# STM32Fx.net
KiCad netlist of a schematic drawn in Altium Designer
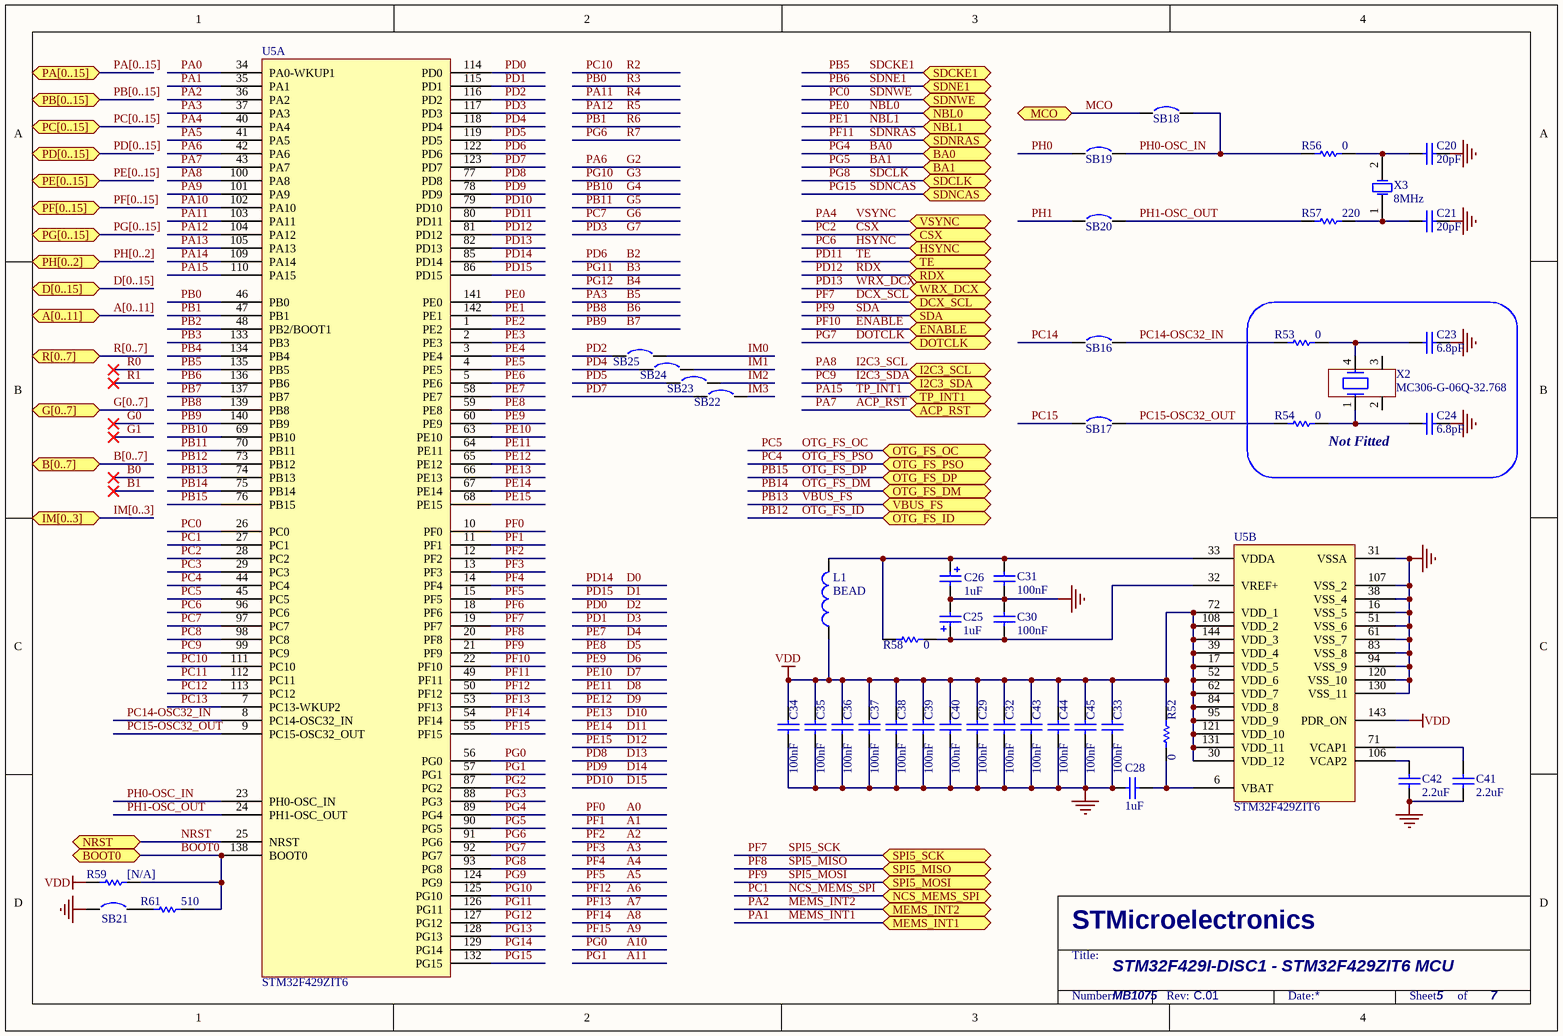
[diagram p0: STM32Fx.SchDoc]

(export (version "E")
  (design (tool "Eeschema 10.0.6"))
  (components
    (comp (ref "C20")
      (value "20pF")
      (footprint "0402C")
      (description "Capacitor 0402 / 0603 / 0805")
      (libsource (lib "MCD_TOOLS") (part "Capacitor_ST"))
    )
    (comp (ref "C21")
      (value "20pF")
      (footprint "0402C")
      (description "Capacitor 0402 / 0603 / 0805")
      (libsource (lib "MCD_TOOLS") (part "Capacitor_ST"))
    )
    (comp (ref "C23")
      (value "6.8pF")
      (footprint "0402C")
      (description "Capacitor 0402 / 0603 / 0805")
      (libsource (lib "MCD_TOOLS") (part "Capacitor_ST"))
    )
    (comp (ref "C24")
      (value "6.8pF")
      (footprint "0402C")
      (description "Capacitor 0402 / 0603 / 0805")
      (libsource (lib "MCD_TOOLS") (part "Capacitor_ST"))
    )
    (comp (ref "C25")
      (value "1uF")
      (footprint "TAN-A")
      (description "Polarized Capacitor (Radial)")
      (fields (field (name "PUBLISHER") "Altium Limited"))
      (libsource (lib "Miscellaneous Devices") (part "Cap Pol1"))
    )
    (comp (ref "C26")
      (value "1uF")
      (footprint "TAN-A")
      (description "Polarized Capacitor (Radial)")
      (fields (field (name "PUBLISHER") "Altium Limited"))
      (libsource (lib "Miscellaneous Devices") (part "Cap Pol1"))
    )
    (comp (ref "C28")
      (value "1uF")
      (footprint "0603C")
      (description "Capacitor 0402 / 0603 / 0805")
      (libsource (lib "MCD_TOOLS") (part "Capacitor_ST"))
    )
    (comp (ref "C29")
      (value "100nF")
      (footprint "0402C")
      (description "Capacitor 0402 / 0603 / 0805")
      (libsource (lib "MCD_TOOLS") (part "Capacitor_ST"))
    )
    (comp (ref "C30")
      (value "100nF")
      (footprint "0402C")
      (description "Capacitor 0402 / 0603 / 0805")
      (libsource (lib "MCD_TOOLS") (part "Capacitor_ST"))
    )
    (comp (ref "C31")
      (value "100nF")
      (footprint "0402C")
      (description "Capacitor 0402 / 0603 / 0805")
      (libsource (lib "MCD_TOOLS") (part "Capacitor_ST"))
    )
    (comp (ref "C32")
      (value "100nF")
      (footprint "0402C")
      (description "Capacitor 0402 / 0603 / 0805")
      (libsource (lib "MCD_TOOLS") (part "Capacitor_ST"))
    )
    (comp (ref "C33")
      (value "100nF")
      (footprint "0402C")
      (description "Capacitor 0402 / 0603 / 0805")
      (libsource (lib "MCD_TOOLS") (part "Capacitor_ST"))
    )
    (comp (ref "C34")
      (value "100nF")
      (footprint "0402C")
      (description "Capacitor 0402 / 0603 / 0805")
      (libsource (lib "MCD_TOOLS") (part "Capacitor_ST"))
    )
    (comp (ref "C35")
      (value "100nF")
      (footprint "0402C")
      (description "Capacitor 0402 / 0603 / 0805")
      (libsource (lib "MCD_TOOLS") (part "Capacitor_ST"))
    )
    (comp (ref "C36")
      (value "100nF")
      (footprint "0402C")
      (description "Capacitor 0402 / 0603 / 0805")
      (libsource (lib "MCD_TOOLS") (part "Capacitor_ST"))
    )
    (comp (ref "C37")
      (value "100nF")
      (footprint "0402C")
      (description "Capacitor 0402 / 0603 / 0805")
      (libsource (lib "MCD_TOOLS") (part "Capacitor_ST"))
    )
    (comp (ref "C38")
      (value "100nF")
      (footprint "0402C")
      (description "Capacitor 0402 / 0603 / 0805")
      (libsource (lib "MCD_TOOLS") (part "Capacitor_ST"))
    )
    (comp (ref "C39")
      (value "100nF")
      (footprint "0402C")
      (description "Capacitor 0402 / 0603 / 0805")
      (libsource (lib "MCD_TOOLS") (part "Capacitor_ST"))
    )
    (comp (ref "C40")
      (value "100nF")
      (footprint "0402C")
      (description "Capacitor 0402 / 0603 / 0805")
      (libsource (lib "MCD_TOOLS") (part "Capacitor_ST"))
    )
    (comp (ref "C41")
      (value "2.2uF")
      (footprint "TAN-A")
      (description "Low ESR Ceramic Capacitor (X7R)")
      (libsource (lib "MCD_TOOLS") (part "Cap Low ESR"))
    )
    (comp (ref "C42")
      (value "2.2uF")
      (footprint "TAN-A")
      (description "Low ESR Ceramic Capacitor (X7R)")
      (libsource (lib "MCD_TOOLS") (part "Cap Low ESR"))
    )
    (comp (ref "C43")
      (value "100nF")
      (footprint "0402C")
      (description "Capacitor 0402 / 0603 / 0805")
      (libsource (lib "MCD_TOOLS") (part "Capacitor_ST"))
    )
    (comp (ref "C44")
      (value "100nF")
      (footprint "0402C")
      (description "Capacitor 0402 / 0603 / 0805")
      (libsource (lib "MCD_TOOLS") (part "Capacitor_ST"))
    )
    (comp (ref "C45")
      (value "100nF")
      (footprint "0402C")
      (description "Capacitor 0402 / 0603 / 0805")
      (libsource (lib "MCD_TOOLS") (part "Capacitor_ST"))
    )
    (comp (ref "L1")
      (value "BEAD")
      (footprint "0603L")
      (description "Inductor")
      (fields (field (name "PUBLISHER") "Altium Limited"))
      (libsource (lib "MCD_TOOLS") (part "Inductor"))
    )
    (comp (ref "R52")
      (value "0")
      (footprint "0402R")
      (description "Resistor 0402 or 0603 or 0805")
      (libsource (lib "MCD_TOOLS") (part "Resistor_ST"))
    )
    (comp (ref "R53")
      (value "0")
      (footprint "0402R")
      (description "Resistor 0402 or 0603 or 0805")
      (libsource (lib "MCD_TOOLS") (part "Resistor_ST"))
    )
    (comp (ref "R54")
      (value "0")
      (footprint "0402R")
      (description "Resistor 0402 or 0603 or 0805")
      (libsource (lib "MCD_TOOLS") (part "Resistor_ST"))
    )
    (comp (ref "R56")
      (value "0")
      (footprint "0402R")
      (description "Resistor 0402 or 0603 or 0805")
      (libsource (lib "MCD_TOOLS") (part "Resistor_ST"))
    )
    (comp (ref "R57")
      (value "220")
      (footprint "0402R")
      (description "Resistor 0402 or 0603 or 0805")
      (libsource (lib "MCD_TOOLS") (part "Resistor_ST"))
    )
    (comp (ref "R58")
      (value "0")
      (footprint "0402R")
      (description "Resistor 0402 or 0603 or 0805")
      (libsource (lib "MCD_TOOLS") (part "Resistor_ST"))
    )
    (comp (ref "R59")
      (value "[N/A]")
      (footprint "0402R")
      (description "Resistor 0402 or 0603 or 0805")
      (libsource (lib "MCD_TOOLS") (part "Resistor_ST"))
    )
    (comp (ref "R61")
      (value "510")
      (footprint "0402R")
      (description "Resistor 0402 or 0603 or 0805")
      (libsource (lib "MCD_TOOLS") (part "Resistor_ST"))
    )
    (comp (ref "SB16")
      (value "Circuit Breaker")
      (footprint "JP2_SMD")
      (fields (field (name "PUBLISHER") "Altium Limited"))
      (libsource (lib "MB915") (part "Circuit Breaker"))
    )
    (comp (ref "SB17")
      (value "Circuit Breaker")
      (footprint "JP2_SMD")
      (fields (field (name "PUBLISHER") "Altium Limited"))
      (libsource (lib "MB915") (part "Circuit Breaker"))
    )
    (comp (ref "SB18")
      (value "Circuit Breaker")
      (footprint "JP2_SMD")
      (fields (field (name "PUBLISHER") "Altium Limited"))
      (libsource (lib "MB915") (part "Circuit Breaker"))
    )
    (comp (ref "SB19")
      (value "Circuit Breaker")
      (footprint "JP2_SMD")
      (fields (field (name "PUBLISHER") "Altium Limited"))
      (libsource (lib "MB915") (part "Circuit Breaker"))
    )
    (comp (ref "SB20")
      (value "Circuit Breaker")
      (footprint "JP2_SMD")
      (fields (field (name "PUBLISHER") "Altium Limited"))
      (libsource (lib "MB915") (part "Circuit Breaker"))
    )
    (comp (ref "SB21")
      (value "Circuit Breaker")
      (footprint "JP2_SMD")
      (fields (field (name "PUBLISHER") "Altium Limited"))
      (libsource (lib "MB915") (part "Circuit Breaker"))
    )
    (comp (ref "SB22")
      (value "Circuit Breaker")
      (footprint "JP2_SMD")
      (fields (field (name "PUBLISHER") "Altium Limited"))
      (libsource (lib "MB915") (part "Circuit Breaker"))
    )
    (comp (ref "SB23")
      (value "Circuit Breaker")
      (footprint "JP2_SMD")
      (fields (field (name "PUBLISHER") "Altium Limited"))
      (libsource (lib "MB915") (part "Circuit Breaker"))
    )
    (comp (ref "SB24")
      (value "Circuit Breaker")
      (footprint "JP2_SMD")
      (fields (field (name "PUBLISHER") "Altium Limited"))
      (libsource (lib "MB915") (part "Circuit Breaker"))
    )
    (comp (ref "SB25")
      (value "Circuit Breaker")
      (footprint "JP2_SMD")
      (fields (field (name "PUBLISHER") "Altium Limited"))
      (libsource (lib "MB915") (part "Circuit Breaker"))
    )
    (comp (ref "U5")
      (value "STM32F429ZIT6")
      (footprint "STM-SMEE:TQFP144")
      (description "STM32 Big Manta (STM32F429ZIT6U)")
      (libsource (lib "MCD_TOOLS") (part "STM32F429ZIT6U"))
    )
    (comp (ref "X2")
      (value "MC306-G-06Q-32.768")
      (footprint "STM-SMEE:MC306-CRYSTAL")
      (description "crystal oscillator for clock,32.768K,6PF,20PPM,-40~85 degree,SMT,ETMB32.768W060BMPF")
      (libsource (lib "MCD_TOOLS") (part "XTAL_32K"))
    )
    (comp (ref "X3")
      (value "8MHz")
      (footprint "STM-SMEE:XTAL1")
      (description "Crystal Oscillator,8Mhz,20PF,20PPM,-10-70 degree,DIP,HC-49S")
      (libsource (lib "MCD_TOOLS") (part "XTAL"))
    )
  )
  (nets
    (net (code "5") (name "/BOOT0") (class "Default")
      (node (ref "R59") (pin "2") (pinfunction "2_2") (pintype "passive"))
      (node (ref "R61") (pin "2") (pinfunction "2_2") (pintype "passive"))
      (node (ref "U5") (pin "138") (pinfunction "BOOT0_138") (pintype "passive"))
    )
    (net (code "11") (name "/IM0") (class "Default")
      (node (ref "SB25") (pin "2") (pinfunction "2_2") (pintype "passive"))
    )
    (net (code "12") (name "/IM1") (class "Default")
      (node (ref "SB24") (pin "2") (pinfunction "2_2") (pintype "passive"))
    )
    (net (code "13") (name "/IM2") (class "Default")
      (node (ref "SB23") (pin "2") (pinfunction "2_2") (pintype "passive"))
    )
    (net (code "14") (name "/IM3") (class "Default")
      (node (ref "SB22") (pin "2") (pinfunction "2_2") (pintype "passive"))
    )
    (net (code "16") (name "/MCO") (class "Default")
      (node (ref "SB18") (pin "1") (pinfunction "1_1") (pintype "passive"))
    )
    (net (code "17") (name "/NRST") (class "Default")
      (node (ref "U5") (pin "25") (pinfunction "NRST_25") (pintype "passive"))
    )
    (net (code "18") (name "/PA0") (class "Default")
      (node (ref "U5") (pin "34") (pinfunction "PA0-WKUP1_34") (pintype "passive"))
    )
    (net (code "19") (name "/PA1") (class "Default")
      (node (ref "U5") (pin "35") (pinfunction "PA1_35") (pintype "passive"))
    )
    (net (code "20") (name "/PA2") (class "Default")
      (node (ref "U5") (pin "36") (pinfunction "PA2_36") (pintype "passive"))
    )
    (net (code "21") (name "/PA3") (class "Default")
      (node (ref "U5") (pin "37") (pinfunction "PA3_37") (pintype "passive"))
    )
    (net (code "22") (name "/PA4") (class "Default")
      (node (ref "U5") (pin "40") (pinfunction "PA4_40") (pintype "passive"))
    )
    (net (code "23") (name "/PA5") (class "Default")
      (node (ref "U5") (pin "41") (pinfunction "PA5_41") (pintype "passive"))
    )
    (net (code "24") (name "/PA6") (class "Default")
      (node (ref "U5") (pin "42") (pinfunction "PA6_42") (pintype "passive"))
    )
    (net (code "25") (name "/PA7") (class "Default")
      (node (ref "U5") (pin "43") (pinfunction "PA7_43") (pintype "passive"))
    )
    (net (code "26") (name "/PA8") (class "Default")
      (node (ref "U5") (pin "100") (pinfunction "PA8_100") (pintype "passive"))
    )
    (net (code "27") (name "/PA9") (class "Default")
      (node (ref "U5") (pin "101") (pinfunction "PA9_101") (pintype "passive"))
    )
    (net (code "28") (name "/PA10") (class "Default")
      (node (ref "U5") (pin "102") (pinfunction "PA10_102") (pintype "passive"))
    )
    (net (code "29") (name "/PA13") (class "Default")
      (node (ref "U5") (pin "105") (pinfunction "PA13_105") (pintype "passive"))
    )
    (net (code "30") (name "/PA14") (class "Default")
      (node (ref "U5") (pin "109") (pinfunction "PA14_109") (pintype "passive"))
    )
    (net (code "31") (name "/PA15") (class "Default")
      (node (ref "U5") (pin "110") (pinfunction "PA15_110") (pintype "passive"))
    )
    (net (code "33") (name "/PB2") (class "Default")
      (node (ref "U5") (pin "48") (pinfunction "PB2/BOOT1_48") (pintype "passive"))
    )
    (net (code "34") (name "/PB3") (class "Default")
      (node (ref "U5") (pin "133") (pinfunction "PB3_133") (pintype "passive"))
    )
    (net (code "35") (name "/PB4") (class "Default")
      (node (ref "U5") (pin "134") (pinfunction "PB4_134") (pintype "passive"))
    )
    (net (code "36") (name "/PB5") (class "Default")
      (node (ref "U5") (pin "135") (pinfunction "PB5_135") (pintype "passive"))
    )
    (net (code "37") (name "/PB6") (class "Default")
      (node (ref "U5") (pin "136") (pinfunction "PB6_136") (pintype "passive"))
    )
    (net (code "38") (name "/PB7") (class "Default")
      (node (ref "U5") (pin "137") (pinfunction "PB7_137") (pintype "passive"))
    )
    (net (code "39") (name "/PB8") (class "Default")
      (node (ref "U5") (pin "139") (pinfunction "PB8_139") (pintype "passive"))
    )
    (net (code "40") (name "/PB9") (class "Default")
      (node (ref "U5") (pin "140") (pinfunction "PB9_140") (pintype "passive"))
    )
    (net (code "41") (name "/PB10") (class "Default")
      (node (ref "U5") (pin "69") (pinfunction "PB10_69") (pintype "passive"))
    )
    (net (code "42") (name "/PB11") (class "Default")
      (node (ref "U5") (pin "70") (pinfunction "PB11_70") (pintype "passive"))
    )
    (net (code "43") (name "/PB12") (class "Default")
      (node (ref "U5") (pin "73") (pinfunction "PB12_73") (pintype "passive"))
    )
    (net (code "44") (name "/PB13") (class "Default")
      (node (ref "U5") (pin "74") (pinfunction "PB13_74") (pintype "passive"))
    )
    (net (code "45") (name "/PB14") (class "Default")
      (node (ref "U5") (pin "75") (pinfunction "PB14_75") (pintype "passive"))
    )
    (net (code "46") (name "/PB15") (class "Default")
      (node (ref "U5") (pin "76") (pinfunction "PB15_76") (pintype "passive"))
    )
    (net (code "48") (name "/PC0") (class "Default")
      (node (ref "U5") (pin "26") (pinfunction "PC0_26") (pintype "passive"))
    )
    (net (code "49") (name "/PC1") (class "Default")
      (node (ref "U5") (pin "27") (pinfunction "PC1_27") (pintype "passive"))
    )
    (net (code "50") (name "/PC2") (class "Default")
      (node (ref "U5") (pin "28") (pinfunction "PC2_28") (pintype "passive"))
    )
    (net (code "51") (name "/PC3") (class "Default")
      (node (ref "U5") (pin "29") (pinfunction "PC3_29") (pintype "passive"))
    )
    (net (code "52") (name "/PC4") (class "Default")
      (node (ref "U5") (pin "44") (pinfunction "PC4_44") (pintype "passive"))
    )
    (net (code "53") (name "/PC5") (class "Default")
      (node (ref "U5") (pin "45") (pinfunction "PC5_45") (pintype "passive"))
    )
    (net (code "54") (name "/PC6") (class "Default")
      (node (ref "U5") (pin "96") (pinfunction "PC6_96") (pintype "passive"))
    )
    (net (code "55") (name "/PC7") (class "Default")
      (node (ref "U5") (pin "97") (pinfunction "PC7_97") (pintype "passive"))
    )
    (net (code "56") (name "/PC8") (class "Default")
      (node (ref "U5") (pin "98") (pinfunction "PC8_98") (pintype "passive"))
    )
    (net (code "57") (name "/PC9") (class "Default")
      (node (ref "U5") (pin "99") (pinfunction "PC9_99") (pintype "passive"))
    )
    (net (code "58") (name "/PC10") (class "Default")
      (node (ref "U5") (pin "111") (pinfunction "PC10_111") (pintype "passive"))
    )
    (net (code "59") (name "/PC11") (class "Default")
      (node (ref "U5") (pin "112") (pinfunction "PC11_112") (pintype "passive"))
    )
    (net (code "60") (name "/PC12") (class "Default")
      (node (ref "U5") (pin "113") (pinfunction "PC12_113") (pintype "passive"))
    )
    (net (code "61") (name "/PC13") (class "Default")
      (node (ref "U5") (pin "7") (pinfunction "PC13-WKUP2_7") (pintype "passive"))
    )
    (net (code "62") (name "/PC14") (class "Default")
      (node (ref "SB16") (pin "1") (pinfunction "1_1") (pintype "passive"))
    )
    (net (code "63") (name "/PC14-OSC32_IN") (class "Default")
      (node (ref "R53") (pin "1") (pinfunction "1_1") (pintype "passive"))
      (node (ref "SB16") (pin "2") (pinfunction "2_2") (pintype "passive"))
      (node (ref "U5") (pin "8") (pinfunction "PC14-OSC32_IN_8") (pintype "passive"))
    )
    (net (code "64") (name "/PC15") (class "Default")
      (node (ref "SB17") (pin "1") (pinfunction "1_1") (pintype "passive"))
    )
    (net (code "65") (name "/PC15-OSC32_OUT") (class "Default")
      (node (ref "R54") (pin "1") (pinfunction "1_1") (pintype "passive"))
      (node (ref "SB17") (pin "2") (pinfunction "2_2") (pintype "passive"))
      (node (ref "U5") (pin "9") (pinfunction "PC15-OSC32_OUT_9") (pintype "passive"))
    )
    (net (code "67") (name "/PD0") (class "Default")
      (node (ref "U5") (pin "114") (pinfunction "PD0_114") (pintype "passive"))
    )
    (net (code "68") (name "/PD1") (class "Default")
      (node (ref "U5") (pin "115") (pinfunction "PD1_115") (pintype "passive"))
    )
    (net (code "69") (name "/PD2") (class "Default")
      (node (ref "SB25") (pin "1") (pinfunction "1_1") (pintype "passive"))
      (node (ref "U5") (pin "116") (pinfunction "PD2_116") (pintype "passive"))
    )
    (net (code "70") (name "/PD3") (class "Default")
      (node (ref "U5") (pin "117") (pinfunction "PD3_117") (pintype "passive"))
    )
    (net (code "71") (name "/PD4") (class "Default")
      (node (ref "SB24") (pin "1") (pinfunction "1_1") (pintype "passive"))
      (node (ref "U5") (pin "118") (pinfunction "PD4_118") (pintype "passive"))
    )
    (net (code "72") (name "/PD5") (class "Default")
      (node (ref "SB23") (pin "1") (pinfunction "1_1") (pintype "passive"))
      (node (ref "U5") (pin "119") (pinfunction "PD5_119") (pintype "passive"))
    )
    (net (code "73") (name "/PD6") (class "Default")
      (node (ref "U5") (pin "122") (pinfunction "PD6_122") (pintype "passive"))
    )
    (net (code "74") (name "/PD7") (class "Default")
      (node (ref "SB22") (pin "1") (pinfunction "1_1") (pintype "passive"))
      (node (ref "U5") (pin "123") (pinfunction "PD7_123") (pintype "passive"))
    )
    (net (code "75") (name "/PD8") (class "Default")
      (node (ref "U5") (pin "77") (pinfunction "PD8_77") (pintype "passive"))
    )
    (net (code "76") (name "/PD9") (class "Default")
      (node (ref "U5") (pin "78") (pinfunction "PD9_78") (pintype "passive"))
    )
    (net (code "77") (name "/PD10") (class "Default")
      (node (ref "U5") (pin "79") (pinfunction "PD10_79") (pintype "passive"))
    )
    (net (code "78") (name "/PD11") (class "Default")
      (node (ref "U5") (pin "80") (pinfunction "PD11_80") (pintype "passive"))
    )
    (net (code "79") (name "/PD12") (class "Default")
      (node (ref "U5") (pin "81") (pinfunction "PD12_81") (pintype "passive"))
    )
    (net (code "80") (name "/PD13") (class "Default")
      (node (ref "U5") (pin "82") (pinfunction "PD13_82") (pintype "passive"))
    )
    (net (code "81") (name "/PD14") (class "Default")
      (node (ref "U5") (pin "85") (pinfunction "PD14_85") (pintype "passive"))
    )
    (net (code "82") (name "/PD15") (class "Default")
      (node (ref "U5") (pin "86") (pinfunction "PD15_86") (pintype "passive"))
    )
    (net (code "84") (name "/PE0") (class "Default")
      (node (ref "U5") (pin "141") (pinfunction "PE0_141") (pintype "passive"))
    )
    (net (code "85") (name "/PE1") (class "Default")
      (node (ref "U5") (pin "142") (pinfunction "PE1_142") (pintype "passive"))
    )
    (net (code "86") (name "/PE2") (class "Default")
      (node (ref "U5") (pin "1") (pinfunction "PE2_1") (pintype "passive"))
    )
    (net (code "87") (name "/PE3") (class "Default")
      (node (ref "U5") (pin "2") (pinfunction "PE3_2") (pintype "passive"))
    )
    (net (code "88") (name "/PE4") (class "Default")
      (node (ref "U5") (pin "3") (pinfunction "PE4_3") (pintype "passive"))
    )
    (net (code "89") (name "/PE5") (class "Default")
      (node (ref "U5") (pin "4") (pinfunction "PE5_4") (pintype "passive"))
    )
    (net (code "90") (name "/PE6") (class "Default")
      (node (ref "U5") (pin "5") (pinfunction "PE6_5") (pintype "passive"))
    )
    (net (code "91") (name "/PE7") (class "Default")
      (node (ref "U5") (pin "58") (pinfunction "PE7_58") (pintype "passive"))
    )
    (net (code "92") (name "/PE8") (class "Default")
      (node (ref "U5") (pin "59") (pinfunction "PE8_59") (pintype "passive"))
    )
    (net (code "93") (name "/PE9") (class "Default")
      (node (ref "U5") (pin "60") (pinfunction "PE9_60") (pintype "passive"))
    )
    (net (code "94") (name "/PE10") (class "Default")
      (node (ref "U5") (pin "63") (pinfunction "PE10_63") (pintype "passive"))
    )
    (net (code "95") (name "/PE11") (class "Default")
      (node (ref "U5") (pin "64") (pinfunction "PE11_64") (pintype "passive"))
    )
    (net (code "96") (name "/PE12") (class "Default")
      (node (ref "U5") (pin "65") (pinfunction "PE12_65") (pintype "passive"))
    )
    (net (code "97") (name "/PE13") (class "Default")
      (node (ref "U5") (pin "66") (pinfunction "PE13_66") (pintype "passive"))
    )
    (net (code "98") (name "/PE14") (class "Default")
      (node (ref "U5") (pin "67") (pinfunction "PE14_67") (pintype "passive"))
    )
    (net (code "99") (name "/PE15") (class "Default")
      (node (ref "U5") (pin "68") (pinfunction "PE15_68") (pintype "passive"))
    )
    (net (code "101") (name "/PF0") (class "Default")
      (node (ref "U5") (pin "10") (pinfunction "PF0_10") (pintype "passive"))
    )
    (net (code "102") (name "/PF1") (class "Default")
      (node (ref "U5") (pin "11") (pinfunction "PF1_11") (pintype "passive"))
    )
    (net (code "103") (name "/PF2") (class "Default")
      (node (ref "U5") (pin "12") (pinfunction "PF2_12") (pintype "passive"))
    )
    (net (code "104") (name "/PF3") (class "Default")
      (node (ref "U5") (pin "13") (pinfunction "PF3_13") (pintype "passive"))
    )
    (net (code "105") (name "/PF4") (class "Default")
      (node (ref "U5") (pin "14") (pinfunction "PF4_14") (pintype "passive"))
    )
    (net (code "106") (name "/PF5") (class "Default")
      (node (ref "U5") (pin "15") (pinfunction "PF5_15") (pintype "passive"))
    )
    (net (code "107") (name "/PF6") (class "Default")
      (node (ref "U5") (pin "18") (pinfunction "PF6_18") (pintype "passive"))
    )
    (net (code "108") (name "/PF7") (class "Default")
      (node (ref "U5") (pin "19") (pinfunction "PF7_19") (pintype "passive"))
    )
    (net (code "109") (name "/PF8") (class "Default")
      (node (ref "U5") (pin "20") (pinfunction "PF8_20") (pintype "passive"))
    )
    (net (code "110") (name "/PF9") (class "Default")
      (node (ref "U5") (pin "21") (pinfunction "PF9_21") (pintype "passive"))
    )
    (net (code "111") (name "/PF10") (class "Default")
      (node (ref "U5") (pin "22") (pinfunction "PF10_22") (pintype "passive"))
    )
    (net (code "112") (name "/PF11") (class "Default")
      (node (ref "U5") (pin "49") (pinfunction "PF11_49") (pintype "passive"))
    )
    (net (code "113") (name "/PF12") (class "Default")
      (node (ref "U5") (pin "50") (pinfunction "PF12_50") (pintype "passive"))
    )
    (net (code "114") (name "/PF13") (class "Default")
      (node (ref "U5") (pin "53") (pinfunction "PF13_53") (pintype "passive"))
    )
    (net (code "115") (name "/PF14") (class "Default")
      (node (ref "U5") (pin "54") (pinfunction "PF14_54") (pintype "passive"))
    )
    (net (code "116") (name "/PF15") (class "Default")
      (node (ref "U5") (pin "55") (pinfunction "PF15_55") (pintype "passive"))
    )
    (net (code "118") (name "/PG0") (class "Default")
      (node (ref "U5") (pin "56") (pinfunction "PG0_56") (pintype "passive"))
    )
    (net (code "119") (name "/PG1") (class "Default")
      (node (ref "U5") (pin "57") (pinfunction "PG1_57") (pintype "passive"))
    )
    (net (code "120") (name "/PG2") (class "Default")
      (node (ref "U5") (pin "87") (pinfunction "PG2_87") (pintype "passive"))
    )
    (net (code "121") (name "/PG3") (class "Default")
      (node (ref "U5") (pin "88") (pinfunction "PG3_88") (pintype "passive"))
    )
    (net (code "122") (name "/PG4") (class "Default")
      (node (ref "U5") (pin "89") (pinfunction "PG4_89") (pintype "passive"))
    )
    (net (code "123") (name "/PG5") (class "Default")
      (node (ref "U5") (pin "90") (pinfunction "PG5_90") (pintype "passive"))
    )
    (net (code "124") (name "/PG6") (class "Default")
      (node (ref "U5") (pin "91") (pinfunction "PG6_91") (pintype "passive"))
    )
    (net (code "125") (name "/PG7") (class "Default")
      (node (ref "U5") (pin "92") (pinfunction "PG7_92") (pintype "passive"))
    )
    (net (code "126") (name "/PG8") (class "Default")
      (node (ref "U5") (pin "93") (pinfunction "PG8_93") (pintype "passive"))
    )
    (net (code "127") (name "/PG9") (class "Default")
      (node (ref "U5") (pin "124") (pinfunction "PG9_124") (pintype "passive"))
    )
    (net (code "128") (name "/PG10") (class "Default")
      (node (ref "U5") (pin "125") (pinfunction "PG10_125") (pintype "passive"))
    )
    (net (code "129") (name "/PG11") (class "Default")
      (node (ref "U5") (pin "126") (pinfunction "PG11_126") (pintype "passive"))
    )
    (net (code "130") (name "/PG12") (class "Default")
      (node (ref "U5") (pin "127") (pinfunction "PG12_127") (pintype "passive"))
    )
    (net (code "131") (name "/PG13") (class "Default")
      (node (ref "U5") (pin "128") (pinfunction "PG13_128") (pintype "passive"))
    )
    (net (code "132") (name "/PG14") (class "Default")
      (node (ref "U5") (pin "129") (pinfunction "PG14_129") (pintype "passive"))
    )
    (net (code "133") (name "/PG15") (class "Default")
      (node (ref "U5") (pin "132") (pinfunction "PG15_132") (pintype "passive"))
    )
    (net (code "135") (name "/PH0") (class "Default")
      (node (ref "SB19") (pin "1") (pinfunction "1_1") (pintype "passive"))
    )
    (net (code "136") (name "/PH0-OSC_IN") (class "Default")
      (node (ref "R56") (pin "1") (pinfunction "1_1") (pintype "passive"))
      (node (ref "SB18") (pin "2") (pinfunction "2_2") (pintype "passive"))
      (node (ref "SB19") (pin "2") (pinfunction "2_2") (pintype "passive"))
      (node (ref "U5") (pin "23") (pinfunction "PH0-OSC_IN_23") (pintype "passive"))
    )
    (net (code "137") (name "/PH1") (class "Default")
      (node (ref "SB20") (pin "1") (pinfunction "1_1") (pintype "passive"))
    )
    (net (code "138") (name "/PH1-OSC_OUT") (class "Default")
      (node (ref "R57") (pin "1") (pinfunction "1_1") (pintype "passive"))
      (node (ref "SB20") (pin "2") (pinfunction "2_2") (pintype "passive"))
      (node (ref "U5") (pin "24") (pinfunction "PH1-OSC_OUT_24") (pintype "passive"))
    )
    (net (code "142") (name "/R3") (class "Default")
      (node (ref "U5") (pin "46") (pinfunction "PB0_46") (pintype "passive"))
    )
    (net (code "143") (name "/R4") (class "Default")
      (node (ref "U5") (pin "103") (pinfunction "PA11_103") (pintype "passive"))
    )
    (net (code "144") (name "/R5") (class "Default")
      (node (ref "U5") (pin "104") (pinfunction "PA12_104") (pintype "passive"))
    )
    (net (code "145") (name "/R6") (class "Default")
      (node (ref "U5") (pin "47") (pinfunction "PB1_47") (pintype "passive"))
    )
    (net (code "147") (name "GND") (class "Default")
      (node (ref "C20") (pin "2") (pinfunction "2_2") (pintype "passive"))
      (node (ref "C21") (pin "2") (pinfunction "2_2") (pintype "passive"))
      (node (ref "C23") (pin "2") (pinfunction "2_2") (pintype "passive"))
      (node (ref "C24") (pin "2") (pinfunction "2_2") (pintype "passive"))
      (node (ref "C25") (pin "2") (pinfunction "2_2") (pintype "passive"))
      (node (ref "C26") (pin "2") (pinfunction "2_2") (pintype "passive"))
      (node (ref "C28") (pin "1") (pinfunction "1_1") (pintype "passive"))
      (node (ref "C29") (pin "1") (pinfunction "1_1") (pintype "passive"))
      (node (ref "C30") (pin "2") (pinfunction "2_2") (pintype "passive"))
      (node (ref "C31") (pin "1") (pinfunction "1_1") (pintype "passive"))
      (node (ref "C32") (pin "1") (pinfunction "1_1") (pintype "passive"))
      (node (ref "C33") (pin "1") (pinfunction "1_1") (pintype "passive"))
      (node (ref "C34") (pin "1") (pinfunction "1_1") (pintype "passive"))
      (node (ref "C35") (pin "1") (pinfunction "1_1") (pintype "passive"))
      (node (ref "C36") (pin "1") (pinfunction "1_1") (pintype "passive"))
      (node (ref "C37") (pin "1") (pinfunction "1_1") (pintype "passive"))
      (node (ref "C38") (pin "1") (pinfunction "1_1") (pintype "passive"))
      (node (ref "C39") (pin "1") (pinfunction "1_1") (pintype "passive"))
      (node (ref "C40") (pin "1") (pinfunction "1_1") (pintype "passive"))
      (node (ref "C41") (pin "2") (pinfunction "2_2") (pintype "passive"))
      (node (ref "C42") (pin "2") (pinfunction "2_2") (pintype "passive"))
      (node (ref "C43") (pin "1") (pinfunction "1_1") (pintype "passive"))
      (node (ref "C44") (pin "1") (pinfunction "1_1") (pintype "passive"))
      (node (ref "C45") (pin "1") (pinfunction "1_1") (pintype "passive"))
      (node (ref "SB21") (pin "1") (pinfunction "1_1") (pintype "passive"))
      (node (ref "U5") (pin "107") (pinfunction "VSS_2_107") (pintype "passive"))
      (node (ref "U5") (pin "120") (pinfunction "VSS_10_120") (pintype "passive"))
      (node (ref "U5") (pin "130") (pinfunction "VSS_11_130") (pintype "passive"))
      (node (ref "U5") (pin "16") (pinfunction "VSS_5_16") (pintype "passive"))
      (node (ref "U5") (pin "31") (pinfunction "VSSA_31") (pintype "passive"))
      (node (ref "U5") (pin "38") (pinfunction "VSS_4_38") (pintype "passive"))
      (node (ref "U5") (pin "51") (pinfunction "VSS_6_51") (pintype "passive"))
      (node (ref "U5") (pin "61") (pinfunction "VSS_7_61") (pintype "passive"))
      (node (ref "U5") (pin "83") (pinfunction "VSS_8_83") (pintype "passive"))
      (node (ref "U5") (pin "94") (pinfunction "VSS_9_94") (pintype "passive"))
    )
    (net (code "148") (name "Net-(C23-Pad1)") (class "Default")
      (node (ref "C23") (pin "1") (pinfunction "1_1") (pintype "passive"))
      (node (ref "R53") (pin "2") (pinfunction "2_2") (pintype "passive"))
      (node (ref "X2") (pin "4") (pinfunction "4_4") (pintype "passive"))
    )
    (net (code "149") (name "Net-(C24-Pad1)") (class "Default")
      (node (ref "C24") (pin "1") (pinfunction "1_1") (pintype "passive"))
      (node (ref "R54") (pin "2") (pinfunction "2_2") (pintype "passive"))
      (node (ref "X2") (pin "1") (pinfunction "1_1") (pintype "passive"))
    )
    (net (code "150") (name "Net-(R61-Pad1)") (class "Default")
      (node (ref "R61") (pin "1") (pinfunction "1_1") (pintype "passive"))
      (node (ref "SB21") (pin "2") (pinfunction "2_2") (pintype "passive"))
    )
    (net (code "151") (name "Net-(U5B-VBAT)") (class "Default")
      (node (ref "C28") (pin "2") (pinfunction "2_2") (pintype "passive"))
      (node (ref "R52") (pin "1") (pinfunction "1_1") (pintype "passive"))
      (node (ref "U5") (pin "6") (pinfunction "VBAT_6") (pintype "passive"))
    )
    (net (code "152") (name "Net-(U5B-VCAP1)") (class "Default")
      (node (ref "C41") (pin "1") (pinfunction "1_1") (pintype "passive"))
      (node (ref "U5") (pin "71") (pinfunction "VCAP1_71") (pintype "passive"))
    )
    (net (code "153") (name "Net-(U5B-VCAP2)") (class "Default")
      (node (ref "C42") (pin "1") (pinfunction "1_1") (pintype "passive"))
      (node (ref "U5") (pin "106") (pinfunction "VCAP2_106") (pintype "passive"))
    )
    (net (code "154") (name "Net-(U5B-VDDA)") (class "Default")
      (node (ref "C26") (pin "1") (pinfunction "1_1") (pintype "passive"))
      (node (ref "C31") (pin "2") (pinfunction "2_2") (pintype "passive"))
      (node (ref "L1") (pin "2") (pinfunction "2_2") (pintype "passive"))
      (node (ref "R58") (pin "1") (pinfunction "1_1") (pintype "passive"))
      (node (ref "U5") (pin "33") (pinfunction "VDDA_33") (pintype "passive"))
    )
    (net (code "155") (name "Net-(U5B-VREF+)") (class "Default")
      (node (ref "C25") (pin "1") (pinfunction "1_1") (pintype "passive"))
      (node (ref "C30") (pin "1") (pinfunction "1_1") (pintype "passive"))
      (node (ref "R58") (pin "2") (pinfunction "2_2") (pintype "passive"))
      (node (ref "U5") (pin "32") (pinfunction "VREF+_32") (pintype "passive"))
    )
    (net (code "156") (name "Net-(X3-OSC1)") (class "Default")
      (node (ref "C21") (pin "1") (pinfunction "1_1") (pintype "passive"))
      (node (ref "R57") (pin "2") (pinfunction "2_2") (pintype "passive"))
      (node (ref "X3") (pin "1") (pinfunction "OSC1_1") (pintype "passive"))
    )
    (net (code "157") (name "Net-(X3-OSC2)") (class "Default")
      (node (ref "C20") (pin "1") (pinfunction "1_1") (pintype "passive"))
      (node (ref "R56") (pin "2") (pinfunction "2_2") (pintype "passive"))
      (node (ref "X3") (pin "2") (pinfunction "OSC2_2") (pintype "passive"))
    )
    (net (code "158") (name "VDD") (class "Default")
      (node (ref "C29") (pin "2") (pinfunction "2_2") (pintype "passive"))
      (node (ref "C32") (pin "2") (pinfunction "2_2") (pintype "passive"))
      (node (ref "C33") (pin "2") (pinfunction "2_2") (pintype "passive"))
      (node (ref "C34") (pin "2") (pinfunction "2_2") (pintype "passive"))
      (node (ref "C35") (pin "2") (pinfunction "2_2") (pintype "passive"))
      (node (ref "C36") (pin "2") (pinfunction "2_2") (pintype "passive"))
      (node (ref "C37") (pin "2") (pinfunction "2_2") (pintype "passive"))
      (node (ref "C38") (pin "2") (pinfunction "2_2") (pintype "passive"))
      (node (ref "C39") (pin "2") (pinfunction "2_2") (pintype "passive"))
      (node (ref "C40") (pin "2") (pinfunction "2_2") (pintype "passive"))
      (node (ref "C43") (pin "2") (pinfunction "2_2") (pintype "passive"))
      (node (ref "C44") (pin "2") (pinfunction "2_2") (pintype "passive"))
      (node (ref "C45") (pin "2") (pinfunction "2_2") (pintype "passive"))
      (node (ref "L1") (pin "1") (pinfunction "1_1") (pintype "passive"))
      (node (ref "R52") (pin "2") (pinfunction "2_2") (pintype "passive"))
      (node (ref "R59") (pin "1") (pinfunction "1_1") (pintype "passive"))
      (node (ref "U5") (pin "108") (pinfunction "VDD_2_108") (pintype "passive"))
      (node (ref "U5") (pin "121") (pinfunction "VDD_10_121") (pintype "passive"))
      (node (ref "U5") (pin "131") (pinfunction "VDD_11_131") (pintype "passive"))
      (node (ref "U5") (pin "143") (pinfunction "PDR_ON_143") (pintype "passive"))
      (node (ref "U5") (pin "144") (pinfunction "VDD_3_144") (pintype "passive"))
      (node (ref "U5") (pin "17") (pinfunction "VDD_5_17") (pintype "passive"))
      (node (ref "U5") (pin "30") (pinfunction "VDD_12_30") (pintype "passive"))
      (node (ref "U5") (pin "39") (pinfunction "VDD_4_39") (pintype "passive"))
      (node (ref "U5") (pin "52") (pinfunction "VDD_6_52") (pintype "passive"))
      (node (ref "U5") (pin "62") (pinfunction "VDD_7_62") (pintype "passive"))
      (node (ref "U5") (pin "72") (pinfunction "VDD_1_72") (pintype "passive"))
      (node (ref "U5") (pin "84") (pinfunction "VDD_8_84") (pintype "passive"))
      (node (ref "U5") (pin "95") (pinfunction "VDD_9_95") (pintype "passive"))
    )
    (net (code "159") (name "unconnected-(X2-Pad2)") (class "Default")
      (node (ref "X2") (pin "2") (pinfunction "2_2") (pintype "passive"))
    )
    (net (code "160") (name "unconnected-(X2-Pad3)") (class "Default")
      (node (ref "X2") (pin "3") (pinfunction "3_3") (pintype "passive"))
    )
  )
)
